# H3-chip-base.net
KiCad netlist of a schematic drawn in Altium Designer
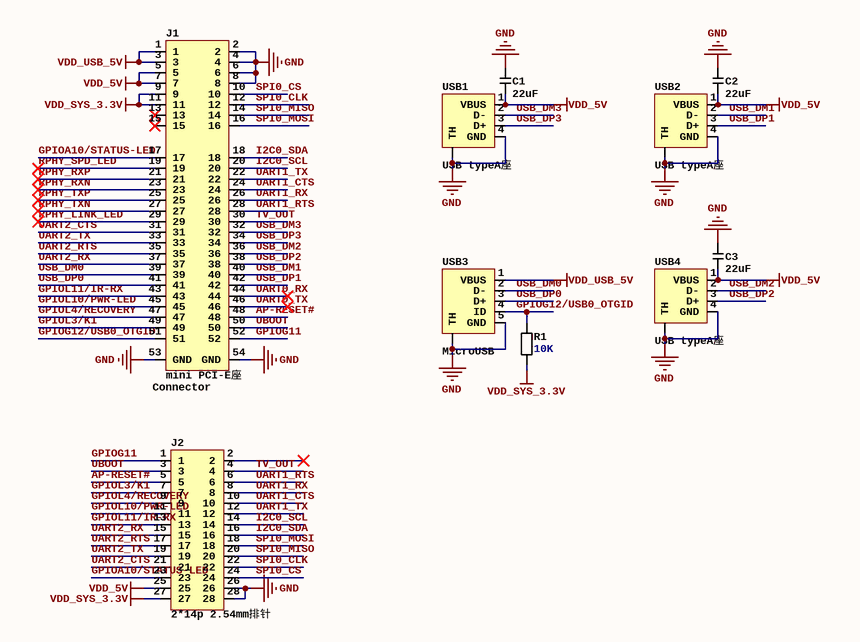
[diagram p0: H3-chip-base.SchDoc]

(export (version "E")
  (design (tool "Eeschema 10.0.6"))
  (components
    (comp (ref "C1")
      (value "22uF")
      (footprint "CAP_0603")
      (description "0603")
      (libsource (lib "myIntlib") (part "CAP_0603_22uF"))
    )
    (comp (ref "C2")
      (value "22uF")
      (footprint "CAP_0603")
      (description "0603")
      (libsource (lib "myIntlib") (part "CAP_0603_22uF"))
    )
    (comp (ref "C3")
      (value "22uF")
      (footprint "CAP_0603")
      (description "0603")
      (libsource (lib "myIntlib") (part "CAP_0603_22uF"))
    )
    (comp (ref "J1")
      (value "mini PCI-E座")
      (footprint "mini PCI-E座")
      (fields (field (name "SYSTEM") "Connector"))
      (libsource (lib "myIntlib") (part "mini PCI-E座"))
    )
    (comp (ref "J2")
      (value "2*14p 2.54mm排针")
      (footprint "2*14p 2.54mm排针")
      (libsource (lib "myIntlib") (part "2*14p 2.54mm排针"))
    )
    (comp (ref "R1")
      (value "10K")
      (footprint "RES_0603")
      (description "0603")
      (libsource (lib "myIntlib") (part "RES_0603_10K"))
    )
    (comp (ref "USB1")
      (value "USB typeA座")
      (footprint "USB typeA座")
      (libsource (lib "myIntlib") (part "USB typeA座"))
    )
    (comp (ref "USB2")
      (value "USB typeA座")
      (footprint "USB typeA座")
      (libsource (lib "myIntlib") (part "USB typeA座"))
    )
    (comp (ref "USB3")
      (value "MicroUSB")
      (footprint "MicroUSB")
      (libsource (lib "myIntlib") (part "MicroUSB"))
    )
    (comp (ref "USB4")
      (value "USB typeA座")
      (footprint "USB typeA座")
      (libsource (lib "myIntlib") (part "USB typeA座"))
    )
  )
  (nets
    (net (code "1") (name "/AP-RESET#") (class "Default")
      (node (ref "J1") (pin "48") (pinfunction "48_48") (pintype "passive"))
      (node (ref "J2") (pin "5") (pinfunction "5_5") (pintype "passive"))
    )
    (net (code "2") (name "/GPIOA10{slash}STATUS-LED") (class "Default")
      (node (ref "J1") (pin "17") (pinfunction "17_17") (pintype "passive"))
      (node (ref "J2") (pin "23") (pinfunction "23_23") (pintype "passive"))
    )
    (net (code "3") (name "/GPIOG11") (class "Default")
      (node (ref "J1") (pin "52") (pinfunction "52_52") (pintype "passive"))
      (node (ref "J2") (pin "1") (pinfunction "1_1") (pintype "passive"))
    )
    (net (code "4") (name "/GPIOG12{slash}USB0_OTGID") (class "Default")
      (node (ref "J1") (pin "51") (pinfunction "51_51") (pintype "passive"))
      (node (ref "R1") (pin "2") (pinfunction "2_2") (pintype "passive"))
      (node (ref "USB3") (pin "4") (pinfunction "ID_4") (pintype "passive"))
    )
    (net (code "5") (name "/GPIOL3{slash}K1") (class "Default")
      (node (ref "J1") (pin "49") (pinfunction "49_49") (pintype "passive"))
      (node (ref "J2") (pin "7") (pinfunction "7_7") (pintype "passive"))
    )
    (net (code "6") (name "/GPIOL4{slash}RECOVERY") (class "Default")
      (node (ref "J1") (pin "47") (pinfunction "47_47") (pintype "passive"))
      (node (ref "J2") (pin "9") (pinfunction "9_9") (pintype "passive"))
    )
    (net (code "7") (name "/GPIOL10{slash}PWR-LED") (class "Default")
      (node (ref "J1") (pin "45") (pinfunction "45_45") (pintype "passive"))
      (node (ref "J2") (pin "11") (pinfunction "11_11") (pintype "passive"))
    )
    (net (code "8") (name "/GPIOL11{slash}IR-RX") (class "Default")
      (node (ref "J1") (pin "43") (pinfunction "43_43") (pintype "passive"))
      (node (ref "J2") (pin "13") (pinfunction "13_13") (pintype "passive"))
    )
    (net (code "9") (name "/I2C0_SCL") (class "Default")
      (node (ref "J1") (pin "20") (pinfunction "20_20") (pintype "passive"))
      (node (ref "J2") (pin "14") (pinfunction "14_14") (pintype "passive"))
    )
    (net (code "10") (name "/I2C0_SDA") (class "Default")
      (node (ref "J1") (pin "18") (pinfunction "18_18") (pintype "passive"))
      (node (ref "J2") (pin "16") (pinfunction "16_16") (pintype "passive"))
    )
    (net (code "11") (name "/RPHY_LINK_LED") (class "Default")
      (node (ref "J1") (pin "29") (pinfunction "29_29") (pintype "passive+no_connect"))
    )
    (net (code "12") (name "/RPHY_RXN") (class "Default")
      (node (ref "J1") (pin "23") (pinfunction "23_23") (pintype "passive+no_connect"))
    )
    (net (code "13") (name "/RPHY_RXP") (class "Default")
      (node (ref "J1") (pin "21") (pinfunction "21_21") (pintype "passive+no_connect"))
    )
    (net (code "14") (name "/RPHY_SPD_LED") (class "Default")
      (node (ref "J1") (pin "19") (pinfunction "19_19") (pintype "passive+no_connect"))
    )
    (net (code "15") (name "/RPHY_TXN") (class "Default")
      (node (ref "J1") (pin "27") (pinfunction "27_27") (pintype "passive+no_connect"))
    )
    (net (code "16") (name "/RPHY_TXP") (class "Default")
      (node (ref "J1") (pin "25") (pinfunction "25_25") (pintype "passive+no_connect"))
    )
    (net (code "17") (name "/SPI0_CLK") (class "Default")
      (node (ref "J1") (pin "12") (pinfunction "12_12") (pintype "passive"))
      (node (ref "J2") (pin "22") (pinfunction "22_22") (pintype "passive"))
    )
    (net (code "18") (name "/SPI0_CS") (class "Default")
      (node (ref "J1") (pin "10") (pinfunction "10_10") (pintype "passive"))
      (node (ref "J2") (pin "24") (pinfunction "24_24") (pintype "passive"))
    )
    (net (code "19") (name "/SPI0_MISO") (class "Default")
      (node (ref "J1") (pin "14") (pinfunction "14_14") (pintype "passive"))
      (node (ref "J2") (pin "20") (pinfunction "20_20") (pintype "passive"))
    )
    (net (code "20") (name "/SPI0_MOSI") (class "Default")
      (node (ref "J1") (pin "16") (pinfunction "16_16") (pintype "passive"))
      (node (ref "J2") (pin "18") (pinfunction "18_18") (pintype "passive"))
    )
    (net (code "21") (name "/TV_OUT") (class "Default")
      (node (ref "J1") (pin "30") (pinfunction "30_30") (pintype "passive"))
      (node (ref "J2") (pin "4") (pinfunction "4_4") (pintype "passive"))
    )
    (net (code "22") (name "/UART0_RX") (class "Default")
      (node (ref "J1") (pin "44") (pinfunction "44_44") (pintype "passive+no_connect"))
    )
    (net (code "23") (name "/UART0_TX") (class "Default")
      (node (ref "J1") (pin "46") (pinfunction "46_46") (pintype "passive+no_connect"))
    )
    (net (code "24") (name "/UART1_CTS") (class "Default")
      (node (ref "J1") (pin "24") (pinfunction "24_24") (pintype "passive"))
      (node (ref "J2") (pin "10") (pinfunction "10_10") (pintype "passive"))
    )
    (net (code "25") (name "/UART1_RTS") (class "Default")
      (node (ref "J1") (pin "28") (pinfunction "28_28") (pintype "passive"))
      (node (ref "J2") (pin "6") (pinfunction "6_6") (pintype "passive"))
    )
    (net (code "26") (name "/UART1_RX") (class "Default")
      (node (ref "J1") (pin "26") (pinfunction "26_26") (pintype "passive"))
      (node (ref "J2") (pin "8") (pinfunction "8_8") (pintype "passive"))
    )
    (net (code "27") (name "/UART1_TX") (class "Default")
      (node (ref "J1") (pin "22") (pinfunction "22_22") (pintype "passive"))
      (node (ref "J2") (pin "12") (pinfunction "12_12") (pintype "passive"))
    )
    (net (code "28") (name "/UART2_CTS") (class "Default")
      (node (ref "J1") (pin "31") (pinfunction "31_31") (pintype "passive"))
      (node (ref "J2") (pin "21") (pinfunction "21_21") (pintype "passive"))
    )
    (net (code "29") (name "/UART2_RTS") (class "Default")
      (node (ref "J1") (pin "35") (pinfunction "35_35") (pintype "passive"))
      (node (ref "J2") (pin "17") (pinfunction "17_17") (pintype "passive"))
    )
    (net (code "30") (name "/UART2_RX") (class "Default")
      (node (ref "J1") (pin "37") (pinfunction "37_37") (pintype "passive"))
      (node (ref "J2") (pin "15") (pinfunction "15_15") (pintype "passive"))
    )
    (net (code "31") (name "/UART2_TX") (class "Default")
      (node (ref "J1") (pin "33") (pinfunction "33_33") (pintype "passive"))
      (node (ref "J2") (pin "19") (pinfunction "19_19") (pintype "passive"))
    )
    (net (code "32") (name "/UBOOT") (class "Default")
      (node (ref "J1") (pin "50") (pinfunction "50_50") (pintype "passive"))
      (node (ref "J2") (pin "3") (pinfunction "3_3") (pintype "passive"))
    )
    (net (code "33") (name "/USB_DM0") (class "Default")
      (node (ref "J1") (pin "39") (pinfunction "39_39") (pintype "passive"))
      (node (ref "USB3") (pin "2") (pinfunction "D-_2") (pintype "passive"))
    )
    (net (code "34") (name "/USB_DM1") (class "Default")
      (node (ref "J1") (pin "40") (pinfunction "40_40") (pintype "passive"))
      (node (ref "USB2") (pin "2") (pinfunction "D-_2") (pintype "passive"))
    )
    (net (code "35") (name "/USB_DM2") (class "Default")
      (node (ref "J1") (pin "36") (pinfunction "36_36") (pintype "passive"))
      (node (ref "USB4") (pin "2") (pinfunction "D-_2") (pintype "passive"))
    )
    (net (code "36") (name "/USB_DM3") (class "Default")
      (node (ref "J1") (pin "32") (pinfunction "32_32") (pintype "passive"))
      (node (ref "USB1") (pin "2") (pinfunction "D-_2") (pintype "passive"))
    )
    (net (code "37") (name "/USB_DP0") (class "Default")
      (node (ref "J1") (pin "41") (pinfunction "41_41") (pintype "passive"))
      (node (ref "USB3") (pin "3") (pinfunction "D+_3") (pintype "passive"))
    )
    (net (code "38") (name "/USB_DP1") (class "Default")
      (node (ref "J1") (pin "42") (pinfunction "42_42") (pintype "passive"))
      (node (ref "USB2") (pin "3") (pinfunction "D+_3") (pintype "passive"))
    )
    (net (code "39") (name "/USB_DP2") (class "Default")
      (node (ref "J1") (pin "38") (pinfunction "38_38") (pintype "passive"))
      (node (ref "USB4") (pin "3") (pinfunction "D+_3") (pintype "passive"))
    )
    (net (code "40") (name "/USB_DP3") (class "Default")
      (node (ref "J1") (pin "34") (pinfunction "34_34") (pintype "passive"))
      (node (ref "USB1") (pin "3") (pinfunction "D+_3") (pintype "passive"))
    )
    (net (code "41") (name "GND") (class "Default")
      (node (ref "C1") (pin "2") (pinfunction "2_2") (pintype "passive"))
      (node (ref "C2") (pin "2") (pinfunction "2_2") (pintype "passive"))
      (node (ref "C3") (pin "2") (pinfunction "2_2") (pintype "passive"))
      (node (ref "J1") (pin "2") (pinfunction "2_2") (pintype "passive"))
      (node (ref "J1") (pin "4") (pinfunction "4_4") (pintype "passive"))
      (node (ref "J1") (pin "53") (pinfunction "GND_53") (pintype "passive"))
      (node (ref "J1") (pin "54") (pinfunction "GND_54") (pintype "passive"))
      (node (ref "J1") (pin "6") (pinfunction "6_6") (pintype "passive"))
      (node (ref "J1") (pin "8") (pinfunction "8_8") (pintype "passive"))
      (node (ref "J2") (pin "26") (pinfunction "26_26") (pintype "passive"))
      (node (ref "J2") (pin "28") (pinfunction "28_28") (pintype "passive"))
      (node (ref "USB1") (pin "0") (pinfunction "TH_0") (pintype "passive"))
      (node (ref "USB1") (pin "4") (pinfunction "GND_4") (pintype "passive"))
      (node (ref "USB2") (pin "0") (pinfunction "TH_0") (pintype "passive"))
      (node (ref "USB2") (pin "4") (pinfunction "GND_4") (pintype "passive"))
      (node (ref "USB3") (pin "0") (pinfunction "TH_0") (pintype "passive"))
      (node (ref "USB3") (pin "5") (pinfunction "GND_5") (pintype "passive"))
      (node (ref "USB4") (pin "0") (pinfunction "TH_0") (pintype "passive"))
      (node (ref "USB4") (pin "4") (pinfunction "GND_4") (pintype "passive"))
    )
    (net (code "42") (name "VDD_5V") (class "Default")
      (node (ref "C1") (pin "1") (pinfunction "1_1") (pintype "passive"))
      (node (ref "C2") (pin "1") (pinfunction "1_1") (pintype "passive"))
      (node (ref "C3") (pin "1") (pinfunction "1_1") (pintype "passive"))
      (node (ref "J1") (pin "5") (pinfunction "5_5") (pintype "passive"))
      (node (ref "J1") (pin "7") (pinfunction "7_7") (pintype "passive"))
      (node (ref "J2") (pin "25") (pinfunction "25_25") (pintype "passive"))
      (node (ref "USB1") (pin "1") (pinfunction "VBUS_1") (pintype "passive"))
      (node (ref "USB2") (pin "1") (pinfunction "VBUS_1") (pintype "passive"))
      (node (ref "USB4") (pin "1") (pinfunction "VBUS_1") (pintype "passive"))
    )
    (net (code "43") (name "VDD_SYS_3.3V") (class "Default")
      (node (ref "J1") (pin "11") (pinfunction "11_11") (pintype "passive"))
      (node (ref "J1") (pin "9") (pinfunction "9_9") (pintype "passive"))
      (node (ref "J2") (pin "27") (pinfunction "27_27") (pintype "passive"))
      (node (ref "R1") (pin "1") (pinfunction "1_1") (pintype "passive"))
    )
    (net (code "44") (name "VDD_USB_5V") (class "Default")
      (node (ref "J1") (pin "1") (pinfunction "1_1") (pintype "passive"))
      (node (ref "J1") (pin "3") (pinfunction "3_3") (pintype "passive"))
      (node (ref "USB3") (pin "1") (pinfunction "VBUS_1") (pintype "passive"))
    )
    (net (code "45") (name "unconnected-(J1-Pad13)") (class "Default")
      (node (ref "J1") (pin "13") (pinfunction "13_13") (pintype "passive+no_connect"))
    )
    (net (code "46") (name "unconnected-(J1-Pad15)") (class "Default")
      (node (ref "J1") (pin "15") (pinfunction "15_15") (pintype "passive+no_connect"))
    )
    (net (code "47") (name "unconnected-(J2-Pad2)") (class "Default")
      (node (ref "J2") (pin "2") (pinfunction "2_2") (pintype "passive+no_connect"))
    )
  )
)
